# IHC.net
KiCad netlist of a schematic drawn in Altium Designer
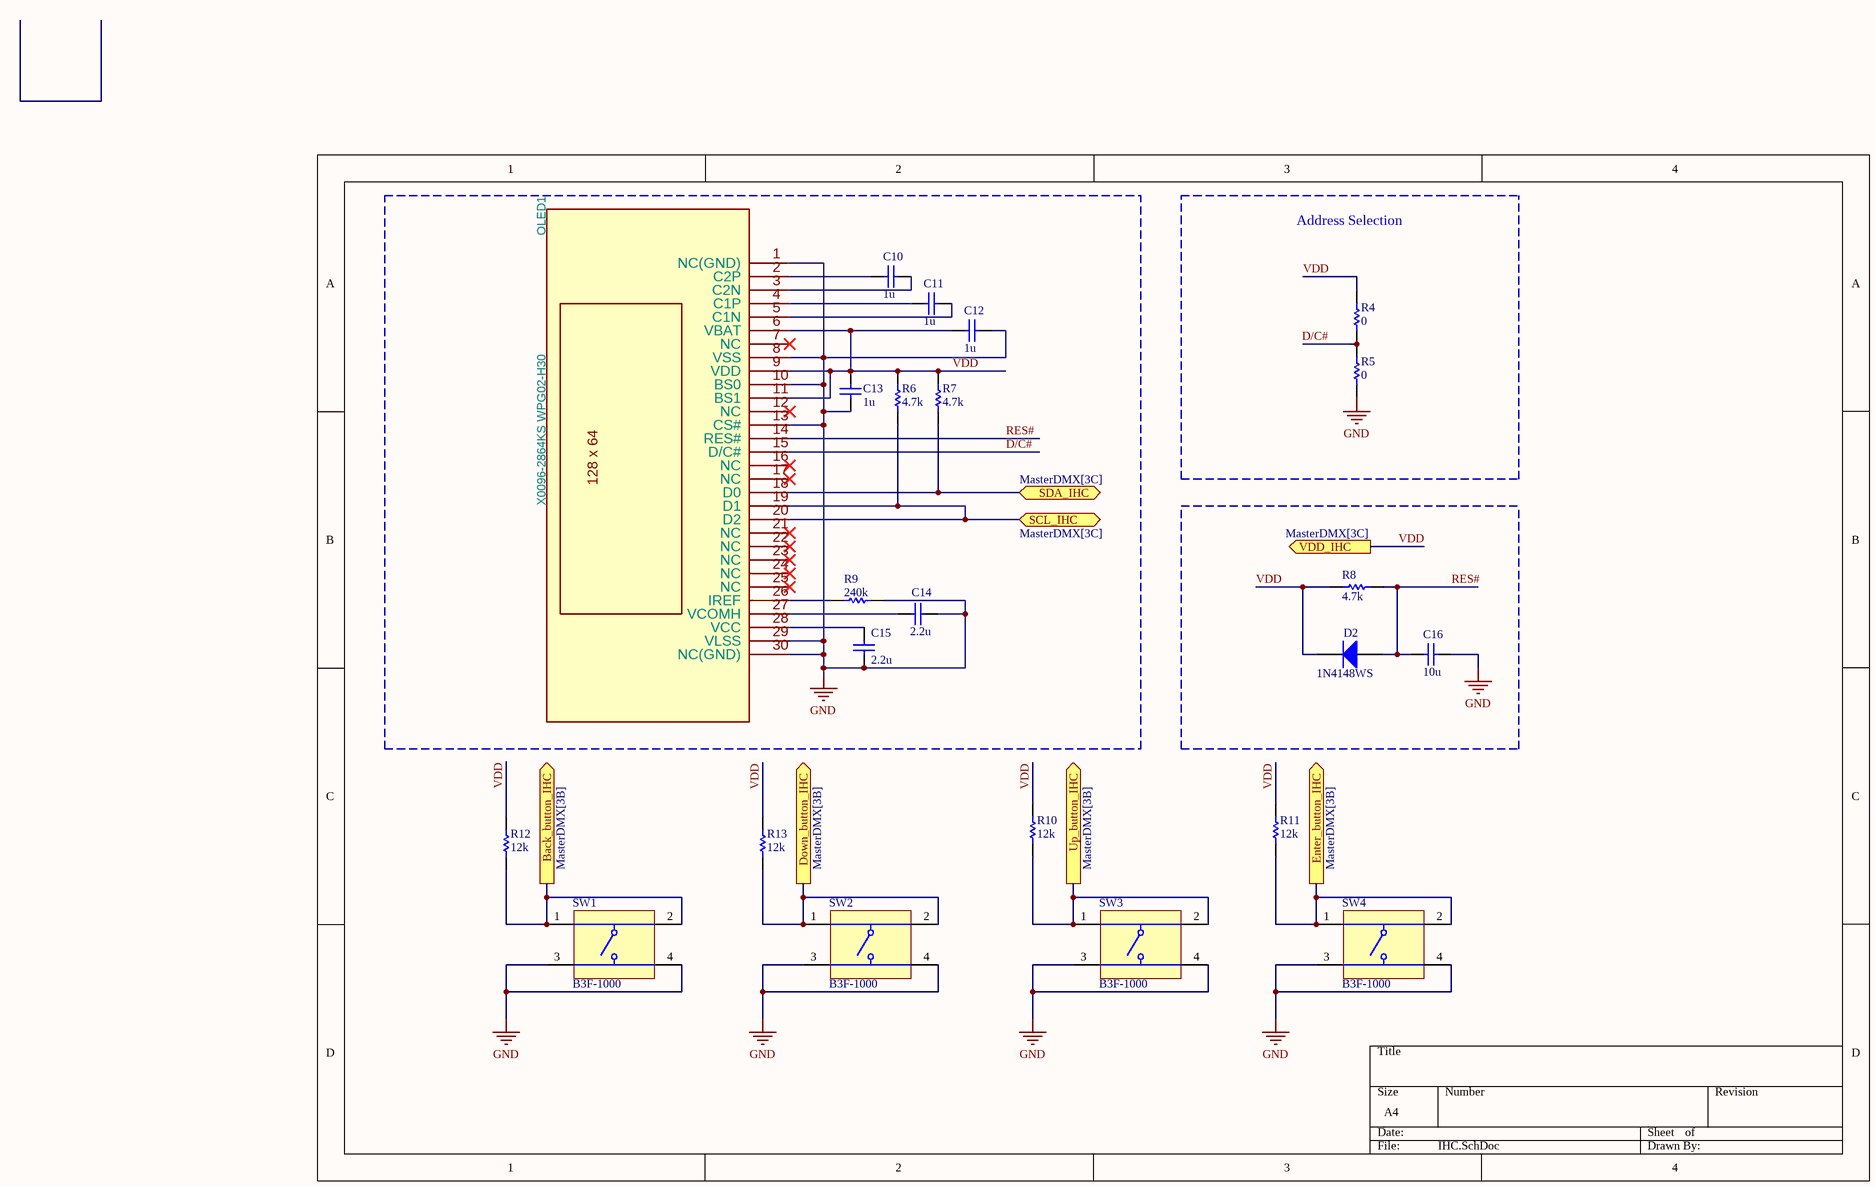
[diagram p0: IHC.SchDoc]

(export (version "E")
  (design (tool "Eeschema 10.0.6"))
  (components
    (comp (ref "C10")
      (value "1u")
      (footprint "C2012[0805]")
      (description "Capacitor")
      (libsource (lib "Basic Library") (part "C"))
    )
    (comp (ref "C11")
      (value "1u")
      (footprint "C2012[0805]")
      (description "Capacitor")
      (libsource (lib "Basic Library") (part "C"))
    )
    (comp (ref "C12")
      (value "1u")
      (footprint "C2012[0805]")
      (description "Capacitor")
      (libsource (lib "Basic Library") (part "C"))
    )
    (comp (ref "C13")
      (value "1u")
      (footprint "C2012[0805]")
      (description "Capacitor")
      (libsource (lib "Basic Library") (part "C"))
    )
    (comp (ref "C14")
      (value "2.2u")
      (footprint "C2012[0805]")
      (description "Capacitor")
      (libsource (lib "Basic Library") (part "C"))
    )
    (comp (ref "C15")
      (value "2.2u")
      (footprint "C2012[0805]")
      (description "Capacitor")
      (libsource (lib "Basic Library") (part "C"))
    )
    (comp (ref "C16")
      (value "10u")
      (footprint "C2012[0805]")
      (description "Capacitor")
      (libsource (lib "Basic Library") (part "C"))
    )
    (comp (ref "D2")
      (value "1N4148WS")
      (footprint "FAIR-SOD-323_V")
      (description "Small Signal Diode, 75 V, 0.15 A, -55 to 150 degC, 2-Pin SOD-323, RoHS, Tape and Reel")
      (fields (field (name "MANUFACTURER") "Fairchild"))
      (libsource (lib "Guilherme Silveira") (part "D-AK-2"))
    )
    (comp (ref "OLED1")
      (value "X0096-2864KS WPG02-H30")
      (footprint "SSD1315_0.96in_30P")
      (libsource (lib "Sheet1-SchDoc-rescue") (part "VG-2864KSWEG01-"))
    )
    (comp (ref "R4")
      (value "0")
      (footprint "R2012[0805]")
      (description "Resistor")
      (libsource (lib "Basic Library") (part "R"))
    )
    (comp (ref "R5")
      (value "0")
      (footprint "R2012[0805]")
      (description "Resistor")
      (libsource (lib "Basic Library") (part "R"))
    )
    (comp (ref "R6")
      (value "4.7k")
      (footprint "R2012[0805]")
      (description "Resistor")
      (libsource (lib "Basic Library") (part "R"))
    )
    (comp (ref "R7")
      (value "4.7k")
      (footprint "R2012[0805]")
      (description "Resistor")
      (libsource (lib "Basic Library") (part "R"))
    )
    (comp (ref "R8")
      (value "4.7k")
      (footprint "R2012[0805]")
      (description "Resistor")
      (libsource (lib "Basic Library") (part "R"))
    )
    (comp (ref "R9")
      (value "240k")
      (footprint "R2012[0805]")
      (description "Resistor")
      (libsource (lib "Basic Library") (part "R"))
    )
    (comp (ref "R10")
      (value "12k")
      (footprint "R2012[0805]")
      (description "Resistor")
      (libsource (lib "Basic Library") (part "R"))
    )
    (comp (ref "R11")
      (value "12k")
      (footprint "R2012[0805]")
      (description "Resistor")
      (libsource (lib "Basic Library") (part "R"))
    )
    (comp (ref "R12")
      (value "12k")
      (footprint "R2012[0805]")
      (description "Resistor")
      (libsource (lib "Basic Library") (part "R"))
    )
    (comp (ref "R13")
      (value "12k")
      (footprint "R2012[0805]")
      (description "Resistor")
      (libsource (lib "Basic Library") (part "R"))
    )
    (comp (ref "SW1")
      (value "B3F-1000")
      (footprint "OMRON-B3F-1000-4_V")
      (description "Tactile Switch, SPST-NO, 0.05 A, 24 V, -25 to 70 degC, 4-Pin THD, RoHS, Bulk")
      (fields (field (name "MANUFACTURER") "Omron Electronic Components"))
      (libsource (lib "Guilherme Silveira") (part "SW-SPST-4_A"))
    )
    (comp (ref "SW2")
      (value "B3F-1000")
      (footprint "OMRON-B3F-1000-4_V")
      (description "Tactile Switch, SPST-NO, 0.05 A, 24 V, -25 to 70 degC, 4-Pin THD, RoHS, Bulk")
      (fields (field (name "MANUFACTURER") "Omron Electronic Components"))
      (libsource (lib "Guilherme Silveira") (part "SW-SPST-4_A"))
    )
    (comp (ref "SW3")
      (value "B3F-1000")
      (footprint "OMRON-B3F-1000-4_V")
      (description "Tactile Switch, SPST-NO, 0.05 A, 24 V, -25 to 70 degC, 4-Pin THD, RoHS, Bulk")
      (fields (field (name "MANUFACTURER") "Omron Electronic Components"))
      (libsource (lib "Guilherme Silveira") (part "SW-SPST-4_A"))
    )
    (comp (ref "SW4")
      (value "B3F-1000")
      (footprint "OMRON-B3F-1000-4_V")
      (description "Tactile Switch, SPST-NO, 0.05 A, 24 V, -25 to 70 degC, 4-Pin THD, RoHS, Bulk")
      (fields (field (name "MANUFACTURER") "Omron Electronic Components"))
      (libsource (lib "Guilherme Silveira") (part "SW-SPST-4_A"))
    )
  )
  (nets
    (net (code "1") (name "/Back_button_IHC") (class "Default")
      (node (ref "R12") (pin "1") (pinfunction "1_1") (pintype "passive"))
      (node (ref "SW1") (pin "1") (pinfunction "1_1") (pintype "passive"))
      (node (ref "SW1") (pin "2") (pinfunction "2_2") (pintype "passive"))
    )
    (net (code "2") (name "/Down_button_IHC") (class "Default")
      (node (ref "R13") (pin "1") (pinfunction "1_1") (pintype "passive"))
      (node (ref "SW2") (pin "1") (pinfunction "1_1") (pintype "passive"))
      (node (ref "SW2") (pin "2") (pinfunction "2_2") (pintype "passive"))
    )
    (net (code "3") (name "/D{slash}C#") (class "Default")
      (node (ref "OLED1") (pin "15") (pinfunction "D/C#_15") (pintype "passive"))
      (node (ref "R4") (pin "1") (pinfunction "1_1") (pintype "passive"))
      (node (ref "R5") (pin "2") (pinfunction "2_2") (pintype "passive"))
    )
    (net (code "4") (name "/Enter_button_IHC") (class "Default")
      (node (ref "R11") (pin "1") (pinfunction "1_1") (pintype "passive"))
      (node (ref "SW4") (pin "1") (pinfunction "1_1") (pintype "passive"))
      (node (ref "SW4") (pin "2") (pinfunction "2_2") (pintype "passive"))
    )
    (net (code "5") (name "/RES#") (class "Default")
      (node (ref "C16") (pin "2") (pinfunction "2_2") (pintype "passive"))
      (node (ref "D2") (pin "1") (pinfunction "A_1") (pintype "passive"))
      (node (ref "OLED1") (pin "14") (pinfunction "RES#_14") (pintype "passive"))
      (node (ref "R8") (pin "1") (pinfunction "1_1") (pintype "passive"))
    )
    (net (code "6") (name "/SCL_IHC") (class "Default")
      (node (ref "OLED1") (pin "19") (pinfunction "D1_19") (pintype "passive"))
      (node (ref "OLED1") (pin "20") (pinfunction "D2_20") (pintype "passive"))
      (node (ref "R6") (pin "1") (pinfunction "1_1") (pintype "passive"))
    )
    (net (code "7") (name "/SDA_IHC") (class "Default")
      (node (ref "OLED1") (pin "18") (pinfunction "D0_18") (pintype "passive"))
      (node (ref "R7") (pin "1") (pinfunction "1_1") (pintype "passive"))
    )
    (net (code "8") (name "/Up_button_IHC") (class "Default")
      (node (ref "R10") (pin "1") (pinfunction "1_1") (pintype "passive"))
      (node (ref "SW3") (pin "1") (pinfunction "1_1") (pintype "passive"))
      (node (ref "SW3") (pin "2") (pinfunction "2_2") (pintype "passive"))
    )
    (net (code "9") (name "/VDD") (class "Default")
      (node (ref "C12") (pin "2") (pinfunction "2_2") (pintype "passive"))
      (node (ref "C13") (pin "1") (pinfunction "1_1") (pintype "passive"))
      (node (ref "D2") (pin "2") (pinfunction "K_2") (pintype "passive"))
      (node (ref "OLED1") (pin "11") (pinfunction "BS1_11") (pintype "passive"))
      (node (ref "OLED1") (pin "6") (pinfunction "VBAT_6") (pintype "passive"))
      (node (ref "OLED1") (pin "9") (pinfunction "VDD_9") (pintype "passive"))
      (node (ref "R10") (pin "2") (pinfunction "2_2") (pintype "passive"))
      (node (ref "R11") (pin "2") (pinfunction "2_2") (pintype "passive"))
      (node (ref "R12") (pin "2") (pinfunction "2_2") (pintype "passive"))
      (node (ref "R13") (pin "2") (pinfunction "2_2") (pintype "passive"))
      (node (ref "R4") (pin "2") (pinfunction "2_2") (pintype "passive"))
      (node (ref "R6") (pin "2") (pinfunction "2_2") (pintype "passive"))
      (node (ref "R7") (pin "2") (pinfunction "2_2") (pintype "passive"))
      (node (ref "R8") (pin "2") (pinfunction "2_2") (pintype "passive"))
    )
    (net (code "10") (name "GND") (class "Default")
      (node (ref "C12") (pin "1") (pinfunction "1_1") (pintype "passive"))
      (node (ref "C13") (pin "2") (pinfunction "2_2") (pintype "passive"))
      (node (ref "C14") (pin "1") (pinfunction "1_1") (pintype "passive"))
      (node (ref "C15") (pin "2") (pinfunction "2_2") (pintype "passive"))
      (node (ref "C16") (pin "1") (pinfunction "1_1") (pintype "passive"))
      (node (ref "OLED1") (pin "1") (pinfunction "NC(GND)_1") (pintype "passive"))
      (node (ref "OLED1") (pin "10") (pinfunction "BS0_10") (pintype "passive"))
      (node (ref "OLED1") (pin "13") (pinfunction "CS#_13") (pintype "passive"))
      (node (ref "OLED1") (pin "29") (pinfunction "VLSS_29") (pintype "passive"))
      (node (ref "OLED1") (pin "30") (pinfunction "NC(GND)_30") (pintype "passive"))
      (node (ref "OLED1") (pin "8") (pinfunction "VSS_8") (pintype "passive"))
      (node (ref "R5") (pin "1") (pinfunction "1_1") (pintype "passive"))
      (node (ref "R9") (pin "2") (pinfunction "2_2") (pintype "passive"))
      (node (ref "SW1") (pin "3") (pinfunction "3_3") (pintype "passive"))
      (node (ref "SW1") (pin "4") (pinfunction "4_4") (pintype "passive"))
      (node (ref "SW2") (pin "3") (pinfunction "3_3") (pintype "passive"))
      (node (ref "SW2") (pin "4") (pinfunction "4_4") (pintype "passive"))
      (node (ref "SW3") (pin "3") (pinfunction "3_3") (pintype "passive"))
      (node (ref "SW3") (pin "4") (pinfunction "4_4") (pintype "passive"))
      (node (ref "SW4") (pin "3") (pinfunction "3_3") (pintype "passive"))
      (node (ref "SW4") (pin "4") (pinfunction "4_4") (pintype "passive"))
    )
    (net (code "11") (name "Net-(OLED1-C1N)") (class "Default")
      (node (ref "C11") (pin "1") (pinfunction "1_1") (pintype "passive"))
      (node (ref "OLED1") (pin "5") (pinfunction "C1N_5") (pintype "passive"))
    )
    (net (code "12") (name "Net-(OLED1-C1P)") (class "Default")
      (node (ref "C11") (pin "2") (pinfunction "2_2") (pintype "passive"))
      (node (ref "OLED1") (pin "4") (pinfunction "C1P_4") (pintype "passive"))
    )
    (net (code "13") (name "Net-(OLED1-C2N)") (class "Default")
      (node (ref "C10") (pin "1") (pinfunction "1_1") (pintype "passive"))
      (node (ref "OLED1") (pin "3") (pinfunction "C2N_3") (pintype "passive"))
    )
    (net (code "14") (name "Net-(OLED1-C2P)") (class "Default")
      (node (ref "C10") (pin "2") (pinfunction "2_2") (pintype "passive"))
      (node (ref "OLED1") (pin "2") (pinfunction "C2P_2") (pintype "passive"))
    )
    (net (code "15") (name "Net-(OLED1-IREF)") (class "Default")
      (node (ref "OLED1") (pin "26") (pinfunction "IREF_26") (pintype "passive"))
      (node (ref "R9") (pin "1") (pinfunction "1_1") (pintype "passive"))
    )
    (net (code "16") (name "Net-(OLED1-VCC)") (class "Default")
      (node (ref "C15") (pin "1") (pinfunction "1_1") (pintype "passive"))
      (node (ref "OLED1") (pin "28") (pinfunction "VCC_28") (pintype "passive"))
    )
    (net (code "17") (name "Net-(OLED1-VCOMH)") (class "Default")
      (node (ref "C14") (pin "2") (pinfunction "2_2") (pintype "passive"))
      (node (ref "OLED1") (pin "27") (pinfunction "VCOMH_27") (pintype "passive"))
    )
    (net (code "18") (name "unconnected-(OLED1-NC-Pad7)") (class "Default")
      (node (ref "OLED1") (pin "7") (pinfunction "NC_7") (pintype "passive+no_connect"))
    )
    (net (code "19") (name "unconnected-(OLED1-NC-Pad12)") (class "Default")
      (node (ref "OLED1") (pin "12") (pinfunction "NC_12") (pintype "passive+no_connect"))
    )
    (net (code "20") (name "unconnected-(OLED1-NC-Pad16)") (class "Default")
      (node (ref "OLED1") (pin "16") (pinfunction "NC_16") (pintype "passive+no_connect"))
    )
    (net (code "21") (name "unconnected-(OLED1-NC-Pad17)") (class "Default")
      (node (ref "OLED1") (pin "17") (pinfunction "NC_17") (pintype "passive+no_connect"))
    )
    (net (code "22") (name "unconnected-(OLED1-NC-Pad21)") (class "Default")
      (node (ref "OLED1") (pin "21") (pinfunction "NC_21") (pintype "passive+no_connect"))
    )
    (net (code "23") (name "unconnected-(OLED1-NC-Pad22)") (class "Default")
      (node (ref "OLED1") (pin "22") (pinfunction "NC_22") (pintype "passive+no_connect"))
    )
    (net (code "24") (name "unconnected-(OLED1-NC-Pad23)") (class "Default")
      (node (ref "OLED1") (pin "23") (pinfunction "NC_23") (pintype "passive+no_connect"))
    )
    (net (code "25") (name "unconnected-(OLED1-NC-Pad24)") (class "Default")
      (node (ref "OLED1") (pin "24") (pinfunction "NC_24") (pintype "passive+no_connect"))
    )
    (net (code "26") (name "unconnected-(OLED1-NC-Pad25)") (class "Default")
      (node (ref "OLED1") (pin "25") (pinfunction "NC_25") (pintype "passive+no_connect"))
    )
  )
)
